# esquema.net
KiCad netlist of a schematic drawn in Altium Designer
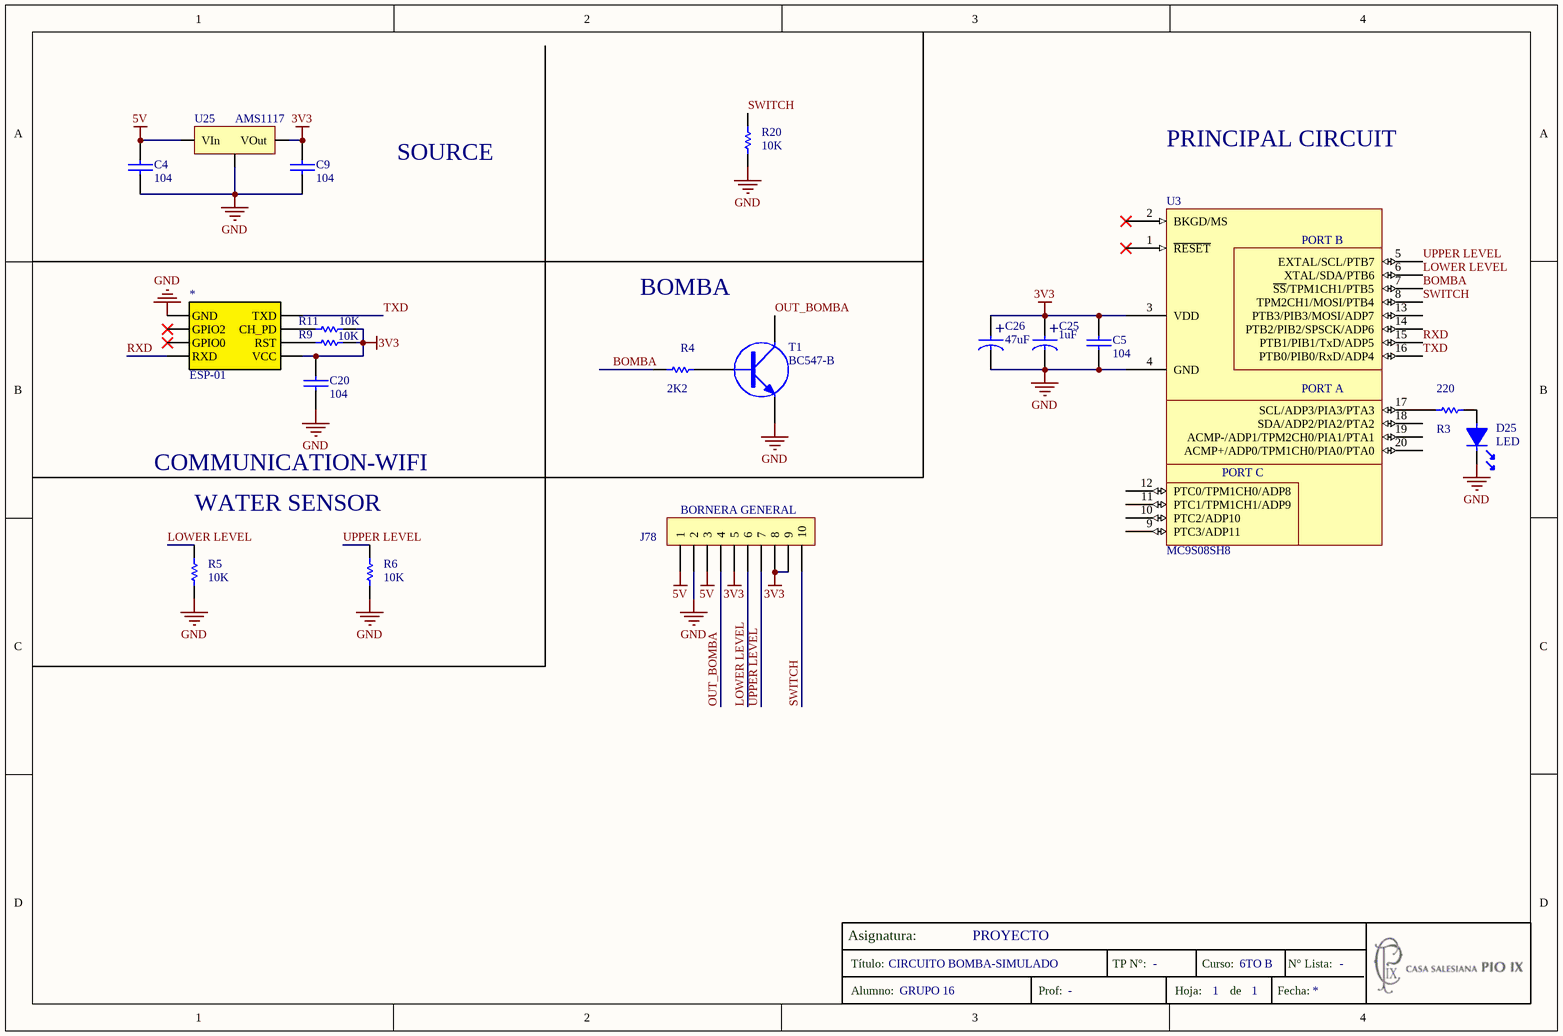
[diagram p0: esquema.SchDoc]

(export (version "E")
  (design (tool "Eeschema 10.0.6"))
  (components
    (comp (ref "*") (value "ESP-01") (footprint "ESP-01") (libsource (lib "Schlib1") (part "ESP-01")))
    (comp (ref "C4")
      (value "104")
      (footprint "0805")
      (description "cap")
      (fields (field (name "AUTOR") "Guido Spataro"))
      (libsource (lib "Schlib1") (part "CAP"))
    )
    (comp (ref "C5")
      (value "104")
      (footprint "0805")
      (description "cap")
      (fields (field (name "AUTOR") "Guido Spataro"))
      (libsource (lib "scdlib") (part "CAP"))
    )
    (comp (ref "C9")
      (value "104")
      (footprint "0805")
      (description "cap")
      (fields (field (name "AUTOR") "Guido Spataro"))
      (libsource (lib "Schlib1") (part "CAP"))
    )
    (comp (ref "C20")
      (value "104")
      (footprint "0805")
      (description "cap")
      (fields (field (name "AUTOR") "Guido Spataro"))
      (libsource (lib "Schlib1") (part "CAP"))
    )
    (comp (ref "C25")
      (value "1uF")
      (footprint "CAP_SMD")
      (description "Cap polarizado")
      (libsource (lib "Schlib1") (part "CAPPOL"))
    )
    (comp (ref "C26")
      (value "47uF")
      (footprint "CAP_SMD")
      (description "Cap polarizado")
      (libsource (lib "Schlib1") (part "CAPPOL"))
    )
    (comp (ref "D25") (value "LED") (footprint "conector-led") (libsource (lib "Schlib1") (part "LED")))
    (comp (ref "J78")
      (value "BORNERA GENERAL")
      (footprint "BORNERA10")
      (libsource (lib "Schlib1") (part "BORNERA10"))
    )
    (comp (ref "R3")
      (value "220")
      (footprint "0805")
      (description "Resistencia")
      (fields (field (name "AUTOR") "Guido Spataro"))
      (libsource (lib "Schlib1") (part "RES"))
    )
    (comp (ref "R4")
      (value "2K2")
      (footprint "0805")
      (description "Resistencia")
      (fields (field (name "AUTOR") "Guido Spataro"))
      (libsource (lib "Schlib1") (part "RES"))
    )
    (comp (ref "R5")
      (value "10K")
      (footprint "0805")
      (description "Resistencia")
      (fields (field (name "AUTOR") "Guido Spataro"))
      (libsource (lib "Schlib1") (part "RES"))
    )
    (comp (ref "R6")
      (value "10K")
      (footprint "0805")
      (description "Resistencia")
      (fields (field (name "AUTOR") "Guido Spataro"))
      (libsource (lib "Schlib1") (part "RES"))
    )
    (comp (ref "R9")
      (value "10K")
      (footprint "0805")
      (description "Resistencia")
      (fields (field (name "AUTOR") "Guido Spataro"))
      (libsource (lib "scdlib") (part "RES"))
    )
    (comp (ref "R11")
      (value "10K")
      (footprint "0805")
      (description "Resistencia")
      (fields (field (name "AUTOR") "Guido Spataro"))
      (libsource (lib "scdlib") (part "RES"))
    )
    (comp (ref "R20")
      (value "10K")
      (footprint "0805")
      (description "Resistencia")
      (fields (field (name "AUTOR") "Guido Spataro"))
      (libsource (lib "Schlib1") (part "RES"))
    )
    (comp (ref "T1")
      (value "BC547-B")
      (footprint "SOT23")
      (libsource (lib "Schlib1") (part "TRANSISTOR NPN"))
    )
    (comp (ref "U3")
      (value "MC9S08SH8")
      (footprint "SH8")
      (description "Micro controlador")
      (fields (field (name "AUTOR") "Guido Spataro"))
      (libsource (lib "scdlib") (part "MC9S08SH8"))
    )
    (comp (ref "U25") (value "AMS1117") (footprint "AMS1117") (libsource (lib "Schlib1") (part "AMS1117")))
  )
  (nets
    (net (code "1") (name "/BOMBA") (class "Default")
      (node (ref "R4") (pin "2") (pinfunction "2_2") (pintype "passive"))
      (node (ref "U3") (pin "7") (pinfunction "~{SS}/TPM1CH1/PTB5_7") (pintype "bidirectional"))
    )
    (net (code "2") (name "/LOWER LEVEL") (class "Default")
      (node (ref "J78") (pin "6") (pinfunction "6_6") (pintype "passive"))
      (node (ref "R5") (pin "2") (pinfunction "2_2") (pintype "passive"))
      (node (ref "U3") (pin "6") (pinfunction "XTAL/SDA/PTB6_6") (pintype "bidirectional"))
    )
    (net (code "3") (name "/OUT_BOMBA") (class "Default")
      (node (ref "J78") (pin "4") (pinfunction "4_4") (pintype "passive"))
      (node (ref "T1") (pin "2") (pinfunction "C_2") (pintype "passive"))
    )
    (net (code "4") (name "/RXD") (class "Default")
      (node (ref "*") (pin "4") (pinfunction "RXD_4") (pintype "passive"))
      (node (ref "U3") (pin "15") (pinfunction "PTB1/PIB1/TxD/ADP5_15") (pintype "bidirectional"))
    )
    (net (code "5") (name "/SWITCH") (class "Default")
      (node (ref "J78") (pin "10") (pinfunction "10_10") (pintype "passive"))
      (node (ref "R20") (pin "2") (pinfunction "2_2") (pintype "passive"))
      (node (ref "U3") (pin "8") (pinfunction "TPM2CH1/MOSI/PTB4_8") (pintype "bidirectional"))
    )
    (net (code "6") (name "/TXD") (class "Default")
      (node (ref "*") (pin "5") (pinfunction "TXD_5") (pintype "passive"))
      (node (ref "U3") (pin "16") (pinfunction "PTB0/PIB0/RxD/ADP4_16") (pintype "bidirectional"))
    )
    (net (code "7") (name "/UPPER LEVEL") (class "Default")
      (node (ref "J78") (pin "7") (pinfunction "7_7") (pintype "passive"))
      (node (ref "R6") (pin "2") (pinfunction "2_2") (pintype "passive"))
      (node (ref "U3") (pin "5") (pinfunction "EXTAL/SCL/PTB7_5") (pintype "bidirectional"))
    )
    (net (code "8") (name "3V3") (class "Default")
      (node (ref "*") (pin "8") (pinfunction "VCC_8") (pintype "passive"))
      (node (ref "C20") (pin "1") (pinfunction "1_1") (pintype "passive"))
      (node (ref "C25") (pin "1") (pinfunction "1_1") (pintype "passive"))
      (node (ref "C26") (pin "1") (pinfunction "1_1") (pintype "passive"))
      (node (ref "C5") (pin "2") (pinfunction "2_2") (pintype "passive"))
      (node (ref "C9") (pin "1") (pinfunction "1_1") (pintype "passive"))
      (node (ref "J78") (pin "5") (pinfunction "5_5") (pintype "passive"))
      (node (ref "J78") (pin "8") (pinfunction "8_8") (pintype "passive"))
      (node (ref "J78") (pin "9") (pinfunction "9_9") (pintype "passive"))
      (node (ref "R11") (pin "1") (pinfunction "1_1") (pintype "passive"))
      (node (ref "R9") (pin "1") (pinfunction "1_1") (pintype "passive"))
      (node (ref "U25") (pin "3") (pinfunction "VOut_3") (pintype "passive"))
      (node (ref "U3") (pin "3") (pinfunction "VDD_3") (pintype "passive"))
    )
    (net (code "9") (name "5V") (class "Default")
      (node (ref "C4") (pin "1") (pinfunction "1_1") (pintype "passive"))
      (node (ref "J78") (pin "1") (pinfunction "1_1") (pintype "passive"))
      (node (ref "J78") (pin "3") (pinfunction "3_3") (pintype "passive"))
      (node (ref "U25") (pin "1") (pinfunction "VIn_1") (pintype "passive"))
    )
    (net (code "10") (name "GND") (class "Default")
      (node (ref "*") (pin "1") (pinfunction "GND_1") (pintype "passive"))
      (node (ref "C20") (pin "2") (pinfunction "2_2") (pintype "passive"))
      (node (ref "C25") (pin "2") (pinfunction "2_2") (pintype "passive"))
      (node (ref "C26") (pin "2") (pinfunction "2_2") (pintype "passive"))
      (node (ref "C4") (pin "2") (pinfunction "2_2") (pintype "passive"))
      (node (ref "C5") (pin "1") (pinfunction "1_1") (pintype "passive"))
      (node (ref "C9") (pin "2") (pinfunction "2_2") (pintype "passive"))
      (node (ref "D25") (pin "2") (pinfunction "2_2") (pintype "passive"))
      (node (ref "J78") (pin "2") (pinfunction "2_2") (pintype "passive"))
      (node (ref "R20") (pin "1") (pinfunction "1_1") (pintype "passive"))
      (node (ref "R5") (pin "1") (pinfunction "1_1") (pintype "passive"))
      (node (ref "R6") (pin "1") (pinfunction "1_1") (pintype "passive"))
      (node (ref "T1") (pin "3") (pinfunction "E_3") (pintype "passive"))
      (node (ref "U25") (pin "2") (pinfunction "GND_2") (pintype "passive"))
      (node (ref "U3") (pin "4") (pinfunction "GND_4") (pintype "passive"))
    )
    (net (code "11") (name "Net-(*-CH_PD)") (class "Default")
      (node (ref "*") (pin "6") (pinfunction "CH_PD_6") (pintype "passive"))
      (node (ref "R11") (pin "2") (pinfunction "2_2") (pintype "passive"))
    )
    (net (code "12") (name "Net-(*-RST)") (class "Default")
      (node (ref "*") (pin "7") (pinfunction "RST_7") (pintype "passive"))
      (node (ref "R9") (pin "2") (pinfunction "2_2") (pintype "passive"))
    )
    (net (code "13") (name "Net-(D25-Pad1)") (class "Default")
      (node (ref "D25") (pin "1") (pinfunction "1_1") (pintype "passive"))
      (node (ref "R3") (pin "1") (pinfunction "1_1") (pintype "passive"))
    )
    (net (code "14") (name "Net-(T1-B)") (class "Default")
      (node (ref "R4") (pin "1") (pinfunction "1_1") (pintype "passive"))
      (node (ref "T1") (pin "1") (pinfunction "B_1") (pintype "passive"))
    )
    (net (code "15") (name "Net-(U3-SCL{slash}ADP3{slash}PIA3{slash}PTA3)") (class "Default")
      (node (ref "R3") (pin "2") (pinfunction "2_2") (pintype "passive"))
      (node (ref "U3") (pin "17") (pinfunction "SCL/ADP3/PIA3/PTA3_17") (pintype "bidirectional"))
    )
    (net (code "16") (name "unconnected-(*-GPIO0-Pad3)") (class "Default")
      (node (ref "*") (pin "3") (pinfunction "GPIO0_3") (pintype "passive+no_connect"))
    )
    (net (code "17") (name "unconnected-(*-GPIO2-Pad2)") (class "Default")
      (node (ref "*") (pin "2") (pinfunction "GPIO2_2") (pintype "passive+no_connect"))
    )
    (net (code "18") (name "unconnected-(U3-ACMP+{slash}ADP0{slash}TPM1CH0{slash}PIA0{slash}PTA0-Pad20)") (class "Default")
      (node (ref "U3") (pin "20") (pinfunction "ACMP+/ADP0/TPM1CH0/PIA0/PTA0_20") (pintype "bidirectional"))
    )
    (net (code "19") (name "unconnected-(U3-ACMP-{slash}ADP1{slash}TPM2CH0{slash}PIA1{slash}PTA1-Pad19)") (class "Default")
      (node (ref "U3") (pin "19") (pinfunction "ACMP-/ADP1/TPM2CH0/PIA1/PTA1_19") (pintype "bidirectional"))
    )
    (net (code "20") (name "unconnected-(U3-BKGD{slash}MS-Pad2)") (class "Default")
      (node (ref "U3") (pin "2") (pinfunction "BKGD/MS_2") (pintype "input+no_connect"))
    )
    (net (code "21") (name "unconnected-(U3-PTB2{slash}PIB2{slash}SPSCK{slash}ADP6-Pad14)") (class "Default")
      (node (ref "U3") (pin "14") (pinfunction "PTB2/PIB2/SPSCK/ADP6_14") (pintype "bidirectional"))
    )
    (net (code "22") (name "unconnected-(U3-PTB3{slash}PIB3{slash}MOSI{slash}ADP7-Pad13)") (class "Default")
      (node (ref "U3") (pin "13") (pinfunction "PTB3/PIB3/MOSI/ADP7_13") (pintype "bidirectional"))
    )
    (net (code "23") (name "unconnected-(U3-PTC0{slash}TPM1CH0{slash}ADP8-Pad12)") (class "Default")
      (node (ref "U3") (pin "12") (pinfunction "PTC0/TPM1CH0/ADP8_12") (pintype "bidirectional"))
    )
    (net (code "24") (name "unconnected-(U3-PTC1{slash}TPM1CH1{slash}ADP9-Pad11)") (class "Default")
      (node (ref "U3") (pin "11") (pinfunction "PTC1/TPM1CH1/ADP9_11") (pintype "bidirectional"))
    )
    (net (code "25") (name "unconnected-(U3-PTC2{slash}ADP10-Pad10)") (class "Default")
      (node (ref "U3") (pin "10") (pinfunction "PTC2/ADP10_10") (pintype "bidirectional"))
    )
    (net (code "26") (name "unconnected-(U3-PTC3{slash}ADP11-Pad9)") (class "Default")
      (node (ref "U3") (pin "9") (pinfunction "PTC3/ADP11_9") (pintype "bidirectional"))
    )
    (net (code "27") (name "unconnected-(U3-SDA{slash}ADP2{slash}PIA2{slash}PTA2-Pad18)") (class "Default")
      (node (ref "U3") (pin "18") (pinfunction "SDA/ADP2/PIA2/PTA2_18") (pintype "bidirectional"))
    )
    (net (code "28") (name "unconnected-(U3-~{RESET}-Pad1)") (class "Default")
      (node (ref "U3") (pin "1") (pinfunction "~{RESET}_1") (pintype "input+no_connect"))
    )
  )
)
